# Sheet1.net
KiCad netlist of a schematic drawn in Altium Designer
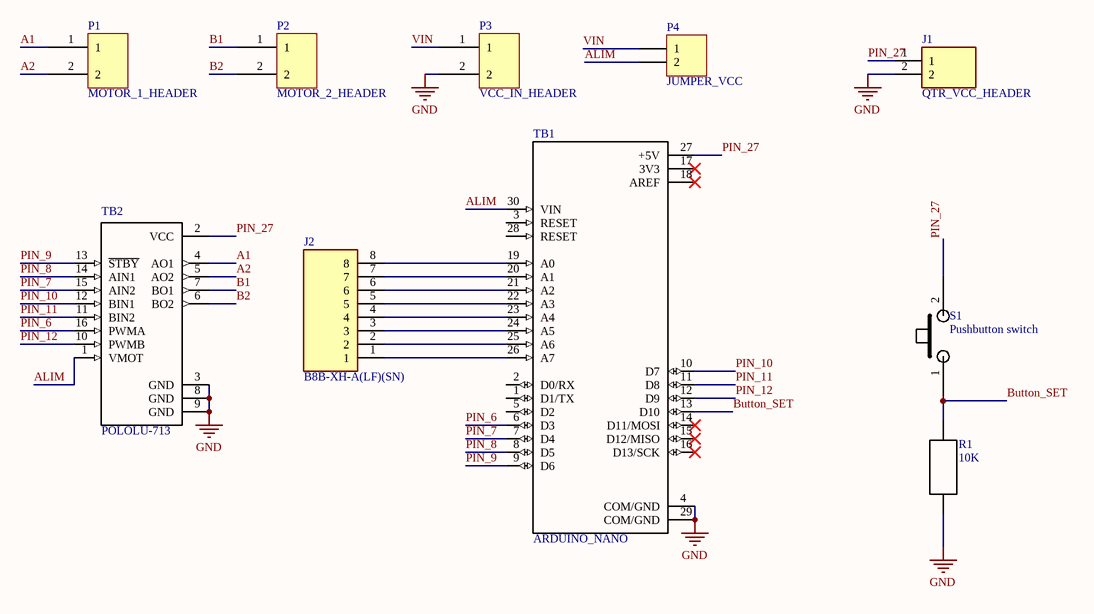
[diagram p0: Sheet1.SchDoc]

(export (version "E")
  (design (tool "Eeschema 10.0.6"))
  (components
    (comp (ref "J1")
      (value "QTR_VCC_HEADER")
      (footprint "SamacSys:SHDR2W64P0X250_1X2_740X575X700P")
      (description "Connector")
      (fields (field (name "MANUFACTURER_PART_NUMBER") "B2B-XH-A(LF)(SN)"))
      (libsource (lib "LibTestSch") (part "B2B-XH-A(LF)(SN)"))
    )
    (comp (ref "J2")
      (value "B8B-XH-A(LF)(SN)")
      (footprint "SamacSys:HDRV8W64P0X250_1X8_2240X575X700P")
      (description "Connector")
      (fields (field (name "RS PART NUMBER") "8201576P"))
      (libsource (lib "LibTestSch") (part "B8B-XH-A(LF)(SN)"))
    )
    (comp (ref "P1")
      (value "MOTOR_1_HEADER")
      (footprint "KRE-2 CONNECTOR")
      (description "KRE _CONNECTOR")
      (libsource (lib "LibTestSch") (part "KRE-2 CONNECTOR"))
    )
    (comp (ref "P2")
      (value "MOTOR_2_HEADER")
      (footprint "KRE-2 CONNECTOR")
      (description "KRE _CONNECTOR")
      (libsource (lib "LibTestSch") (part "KRE-2 CONNECTOR"))
    )
    (comp (ref "P3")
      (value "VCC_IN_HEADER")
      (footprint "KRE-2 CONNECTOR")
      (description "KRE _CONNECTOR")
      (libsource (lib "LibTestSch") (part "KRE-2 CONNECTOR"))
    )
    (comp (ref "P4")
      (value "JUMPER_VCC")
      (footprint "HDR1X2")
      (description "Header, 2-Pin")
      (fields (field (name "PUBLISHER") "Altium Limited"))
      (libsource (lib "Miscellaneous Connectors") (part "Header 2"))
    )
    (comp (ref "R1")
      (value "10K")
      (footprint "Axial 0.4(resistor)")
      (description "RES 10K OHM 1/4W 5% AXIAL")
      (fields (field (name "EVENDORPART#") "10KQTR-ND") (field (name "MANUFACTURER") "Yageo"))
      (libsource (lib "LibTestSch") (part "Resistor 10K"))
    )
    (comp (ref "S1")
      (value "Pushbutton switch")
      (footprint "Pushbutton")
      (fields (field (name "EVENDORPART#") "mota"))
      (libsource (lib "LibTestSch") (part "Pushbutton switch"))
    )
    (comp (ref "TB1")
      (value "ARDUINO_NANO")
      (footprint "*SHIELD_ARDUINO_NANO")
      (description "Dev.kit: Arduino; UART; ICSP, USB B mini, pin strips")
      (fields (field (name "MP") "ARDUINO NANO") (field (name "MF") "Arduino"))
      (libsource (lib "LibTestSch") (part "ARDUINO_NANO"))
    )
    (comp (ref "TB2")
      (value "POLOLU-713")
      (footprint "*SHIELD_POLOLU-713")
      (description "DC-motor driver; IC: TB6612FNG; 100kHz; 1A; Uin mot: 4.5")
      (fields (field (name "MF") "Pololu"))
      (libsource (lib "LibTestSch") (part "POLOLU-713"))
    )
  )
  (nets
    (net (code "1") (name "/A1") (class "Default")
      (node (ref "P1") (pin "1") (pinfunction "1_1") (pintype "passive"))
      (node (ref "TB2") (pin "4") (pinfunction "AO1_4") (pintype "output"))
    )
    (net (code "2") (name "/A2") (class "Default")
      (node (ref "P1") (pin "2") (pinfunction "2_2") (pintype "passive"))
      (node (ref "TB2") (pin "5") (pinfunction "AO2_5") (pintype "output"))
    )
    (net (code "3") (name "/ALIM") (class "Default")
      (node (ref "P4") (pin "2") (pinfunction "2_2") (pintype "passive"))
      (node (ref "TB1") (pin "30") (pinfunction "VIN_30") (pintype "input"))
      (node (ref "TB2") (pin "1") (pinfunction "VMOT_1") (pintype "input"))
    )
    (net (code "4") (name "/B1") (class "Default")
      (node (ref "P2") (pin "1") (pinfunction "1_1") (pintype "passive"))
      (node (ref "TB2") (pin "7") (pinfunction "BO1_7") (pintype "output"))
    )
    (net (code "5") (name "/B2") (class "Default")
      (node (ref "P2") (pin "2") (pinfunction "2_2") (pintype "passive"))
      (node (ref "TB2") (pin "6") (pinfunction "BO2_6") (pintype "output"))
    )
    (net (code "6") (name "/Button_SET") (class "Default")
      (node (ref "R1") (pin "2") (pinfunction "2_2") (pintype "passive"))
      (node (ref "S1") (pin "1") (pinfunction "A_1") (pintype "passive"))
      (node (ref "TB1") (pin "13") (pinfunction "D10_13") (pintype "bidirectional"))
    )
    (net (code "7") (name "/PIN_6") (class "Default")
      (node (ref "TB1") (pin "6") (pinfunction "D3_6") (pintype "bidirectional"))
      (node (ref "TB2") (pin "16") (pinfunction "PWMA_16") (pintype "input"))
    )
    (net (code "8") (name "/PIN_7") (class "Default")
      (node (ref "TB1") (pin "7") (pinfunction "D4_7") (pintype "bidirectional"))
      (node (ref "TB2") (pin "15") (pinfunction "AIN2_15") (pintype "input"))
    )
    (net (code "9") (name "/PIN_8") (class "Default")
      (node (ref "TB1") (pin "8") (pinfunction "D5_8") (pintype "bidirectional"))
      (node (ref "TB2") (pin "14") (pinfunction "AIN1_14") (pintype "input"))
    )
    (net (code "10") (name "/PIN_9") (class "Default")
      (node (ref "TB1") (pin "9") (pinfunction "D6_9") (pintype "bidirectional"))
      (node (ref "TB2") (pin "13") (pinfunction "~{STBY}_13") (pintype "input"))
    )
    (net (code "11") (name "/PIN_10") (class "Default")
      (node (ref "TB1") (pin "10") (pinfunction "D7_10") (pintype "bidirectional"))
      (node (ref "TB2") (pin "12") (pinfunction "BIN1_12") (pintype "input"))
    )
    (net (code "12") (name "/PIN_11") (class "Default")
      (node (ref "TB1") (pin "11") (pinfunction "D8_11") (pintype "bidirectional"))
      (node (ref "TB2") (pin "11") (pinfunction "BIN2_11") (pintype "input"))
    )
    (net (code "13") (name "/PIN_12") (class "Default")
      (node (ref "TB1") (pin "12") (pinfunction "D9_12") (pintype "bidirectional"))
      (node (ref "TB2") (pin "10") (pinfunction "PWMB_10") (pintype "input"))
    )
    (net (code "14") (name "/PIN_27") (class "Default")
      (node (ref "J1") (pin "1") (pinfunction "1_1") (pintype "passive"))
      (node (ref "S1") (pin "2") (pinfunction "B_2") (pintype "passive"))
      (node (ref "TB1") (pin "27") (pinfunction "+5V_27") (pintype "power_in"))
      (node (ref "TB2") (pin "2") (pinfunction "VCC_2") (pintype "power_in"))
    )
    (net (code "15") (name "/VIN") (class "Default")
      (node (ref "P3") (pin "1") (pinfunction "1_1") (pintype "passive"))
      (node (ref "P4") (pin "1") (pinfunction "1_1") (pintype "passive"))
    )
    (net (code "16") (name "GND") (class "Default")
      (node (ref "J1") (pin "2") (pinfunction "2_2") (pintype "passive"))
      (node (ref "P3") (pin "2") (pinfunction "2_2") (pintype "passive"))
      (node (ref "R1") (pin "1") (pinfunction "1_1") (pintype "passive"))
      (node (ref "TB1") (pin "29") (pinfunction "COM/GND_29") (pintype "power_in"))
      (node (ref "TB1") (pin "4") (pinfunction "COM/GND_4") (pintype "power_in"))
      (node (ref "TB2") (pin "3") (pinfunction "GND_3") (pintype "power_in"))
      (node (ref "TB2") (pin "8") (pinfunction "GND_8") (pintype "power_in"))
      (node (ref "TB2") (pin "9") (pinfunction "GND_9") (pintype "power_in"))
    )
    (net (code "17") (name "Net-(TB1-A0)") (class "Default")
      (node (ref "J2") (pin "8") (pinfunction "8_8") (pintype "passive"))
      (node (ref "TB1") (pin "19") (pinfunction "A0_19") (pintype "input"))
    )
    (net (code "18") (name "Net-(TB1-A1)") (class "Default")
      (node (ref "J2") (pin "7") (pinfunction "7_7") (pintype "passive"))
      (node (ref "TB1") (pin "20") (pinfunction "A1_20") (pintype "input"))
    )
    (net (code "19") (name "Net-(TB1-A2)") (class "Default")
      (node (ref "J2") (pin "6") (pinfunction "6_6") (pintype "passive"))
      (node (ref "TB1") (pin "21") (pinfunction "A2_21") (pintype "input"))
    )
    (net (code "20") (name "Net-(TB1-A3)") (class "Default")
      (node (ref "J2") (pin "5") (pinfunction "5_5") (pintype "passive"))
      (node (ref "TB1") (pin "22") (pinfunction "A3_22") (pintype "input"))
    )
    (net (code "21") (name "Net-(TB1-A4)") (class "Default")
      (node (ref "J2") (pin "4") (pinfunction "4_4") (pintype "passive"))
      (node (ref "TB1") (pin "23") (pinfunction "A4_23") (pintype "input"))
    )
    (net (code "22") (name "Net-(TB1-A5)") (class "Default")
      (node (ref "J2") (pin "3") (pinfunction "3_3") (pintype "passive"))
      (node (ref "TB1") (pin "24") (pinfunction "A5_24") (pintype "input"))
    )
    (net (code "23") (name "Net-(TB1-A6)") (class "Default")
      (node (ref "J2") (pin "2") (pinfunction "2_2") (pintype "passive"))
      (node (ref "TB1") (pin "25") (pinfunction "A6_25") (pintype "input"))
    )
    (net (code "24") (name "Net-(TB1-A7)") (class "Default")
      (node (ref "J2") (pin "1") (pinfunction "1_1") (pintype "passive"))
      (node (ref "TB1") (pin "26") (pinfunction "A7_26") (pintype "input"))
    )
    (net (code "25") (name "unconnected-(TB1-3V3-Pad17)") (class "Default")
      (node (ref "TB1") (pin "17") (pinfunction "3V3_17") (pintype "power_in+no_connect"))
    )
    (net (code "26") (name "unconnected-(TB1-AREF-Pad18)") (class "Default")
      (node (ref "TB1") (pin "18") (pinfunction "AREF_18") (pintype "power_in+no_connect"))
    )
    (net (code "27") (name "unconnected-(TB1-D0{slash}RX-Pad2)") (class "Default")
      (node (ref "TB1") (pin "2") (pinfunction "D0/RX_2") (pintype "bidirectional"))
    )
    (net (code "28") (name "unconnected-(TB1-D1{slash}TX-Pad1)") (class "Default")
      (node (ref "TB1") (pin "1") (pinfunction "D1/TX_1") (pintype "bidirectional"))
    )
    (net (code "29") (name "unconnected-(TB1-D2-Pad5)") (class "Default")
      (node (ref "TB1") (pin "5") (pinfunction "D2_5") (pintype "bidirectional"))
    )
    (net (code "30") (name "unconnected-(TB1-D11{slash}MOSI-Pad14)") (class "Default")
      (node (ref "TB1") (pin "14") (pinfunction "D11/MOSI_14") (pintype "bidirectional+no_connect"))
    )
    (net (code "31") (name "unconnected-(TB1-D12{slash}MISO-Pad15)") (class "Default")
      (node (ref "TB1") (pin "15") (pinfunction "D12/MISO_15") (pintype "bidirectional+no_connect"))
    )
    (net (code "32") (name "unconnected-(TB1-D13{slash}SCK-Pad16)") (class "Default")
      (node (ref "TB1") (pin "16") (pinfunction "D13/SCK_16") (pintype "bidirectional+no_connect"))
    )
    (net (code "33") (name "unconnected-(TB1-RESET-Pad3)") (class "Default")
      (node (ref "TB1") (pin "3") (pinfunction "RESET_3") (pintype "input"))
    )
    (net (code "34") (name "unconnected-(TB1-RESET-Pad28)") (class "Default")
      (node (ref "TB1") (pin "28") (pinfunction "RESET_28") (pintype "input"))
    )
  )
)
